# TPS54531.net
KiCad netlist of a schematic drawn in Altium Designer
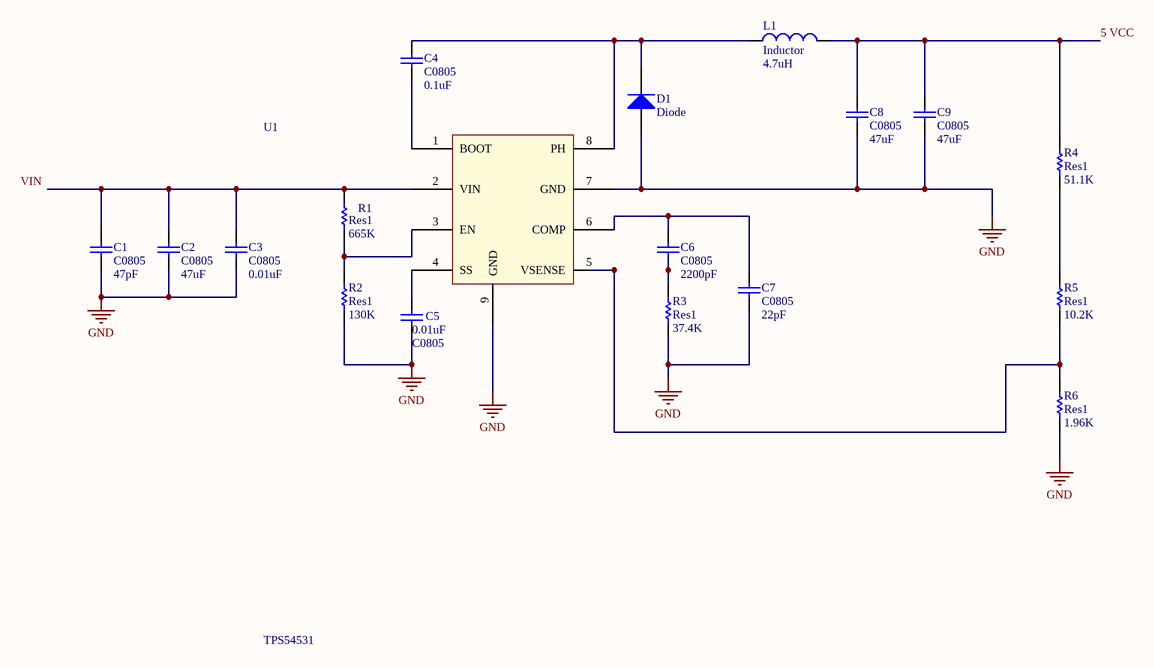
[diagram p0: TPS54531.SchDoc]

(export (version "E")
  (design (tool "Eeschema 10.0.6"))
  (components
    (comp (ref "C1")
      (value "C0805")
      (footprint "0805")
      (description "Ceramic Chip Capacitor - Standard")
      (fields (field (name "ALTIUM_VALUE") "47pF") (field (name "PUBLISHER") "Altium Limited"))
      (libsource (lib "KEMET Chip Capacitor") (part "C0805"))
    )
    (comp (ref "C2")
      (value "C0805")
      (footprint "0805")
      (description "Ceramic Chip Capacitor - Standard")
      (fields (field (name "ALTIUM_VALUE") "47uF") (field (name "PUBLISHER") "Altium Limited"))
      (libsource (lib "KEMET Chip Capacitor") (part "C0805"))
    )
    (comp (ref "C3")
      (value "C0805")
      (footprint "0805")
      (description "Ceramic Chip Capacitor - Standard")
      (fields (field (name "ALTIUM_VALUE") "0.01uF") (field (name "PUBLISHER") "Altium Limited"))
      (libsource (lib "KEMET Chip Capacitor") (part "C0805"))
    )
    (comp (ref "C4")
      (value "C0805")
      (footprint "0805")
      (description "Ceramic Chip Capacitor - Standard")
      (fields (field (name "ALTIUM_VALUE") "0.1uF") (field (name "PUBLISHER") "Altium Limited"))
      (libsource (lib "KEMET Chip Capacitor") (part "C0805"))
    )
    (comp (ref "C5")
      (value "C0805")
      (footprint "0805")
      (description "Ceramic Chip Capacitor - Standard")
      (fields (field (name "ALTIUM_VALUE") "0.01uF") (field (name "PUBLISHER") "Altium Limited"))
      (libsource (lib "KEMET Chip Capacitor") (part "C0805"))
    )
    (comp (ref "C6")
      (value "C0805")
      (footprint "0805")
      (description "Ceramic Chip Capacitor - Standard")
      (fields (field (name "ALTIUM_VALUE") "2200pF") (field (name "PUBLISHER") "Altium Limited"))
      (libsource (lib "KEMET Chip Capacitor") (part "C0805"))
    )
    (comp (ref "C7")
      (value "C0805")
      (footprint "0805")
      (description "Ceramic Chip Capacitor - Standard")
      (fields (field (name "ALTIUM_VALUE") "22pF") (field (name "PUBLISHER") "Altium Limited"))
      (libsource (lib "KEMET Chip Capacitor") (part "C0805"))
    )
    (comp (ref "C8")
      (value "C0805")
      (footprint "0805")
      (description "Ceramic Chip Capacitor - Standard")
      (fields (field (name "ALTIUM_VALUE") "47uF") (field (name "PUBLISHER") "Altium Limited"))
      (libsource (lib "KEMET Chip Capacitor") (part "C0805"))
    )
    (comp (ref "C9")
      (value "C0805")
      (footprint "0805")
      (description "Ceramic Chip Capacitor - Standard")
      (fields (field (name "ALTIUM_VALUE") "47uF") (field (name "PUBLISHER") "Altium Limited"))
      (libsource (lib "KEMET Chip Capacitor") (part "C0805"))
    )
    (comp (ref "D1")
      (value "Diode")
      (footprint "SMC")
      (description "Default Diode")
      (fields (field (name "PUBLISHER") "Altium Limited"))
      (libsource (lib "Miscellaneous Devices") (part "Diode"))
    )
    (comp (ref "L1")
      (value "Inductor")
      (footprint "0402-A")
      (fields (field (name "ALTIUM_VALUE") "4.7uH") (field (name "PUBLISHER") "Altium Limited"))
      (libsource (lib "Miscellaneous Devices") (part "Inductor"))
    )
    (comp (ref "R1")
      (value "Res1")
      (footprint "AXIAL-0.3")
      (description "Resistor")
      (fields (field (name "ALTIUM_VALUE") "665K") (field (name "PUBLISHER") "Altium Limited"))
      (libsource (lib "Miscellaneous Devices") (part "Res1"))
    )
    (comp (ref "R2")
      (value "Res1")
      (footprint "AXIAL-0.3")
      (description "Resistor")
      (fields (field (name "ALTIUM_VALUE") "130K") (field (name "PUBLISHER") "Altium Limited"))
      (libsource (lib "Miscellaneous Devices") (part "Res1"))
    )
    (comp (ref "R3")
      (value "Res1")
      (footprint "AXIAL-0.3")
      (description "Resistor")
      (fields (field (name "ALTIUM_VALUE") "37.4K") (field (name "PUBLISHER") "Altium Limited"))
      (libsource (lib "Miscellaneous Devices") (part "Res1"))
    )
    (comp (ref "R4")
      (value "Res1")
      (footprint "AXIAL-0.3")
      (description "Resistor")
      (fields (field (name "ALTIUM_VALUE") "51.1K") (field (name "PUBLISHER") "Altium Limited"))
      (libsource (lib "Miscellaneous Devices") (part "Res1"))
    )
    (comp (ref "R5")
      (value "Res1")
      (footprint "AXIAL-0.3")
      (description "Resistor")
      (fields (field (name "ALTIUM_VALUE") "10.2K") (field (name "PUBLISHER") "Altium Limited"))
      (libsource (lib "Miscellaneous Devices") (part "Res1"))
    )
    (comp (ref "R6")
      (value "Res1")
      (footprint "AXIAL-0.3")
      (description "Resistor")
      (fields (field (name "ALTIUM_VALUE") "1.96K") (field (name "PUBLISHER") "Altium Limited"))
      (libsource (lib "Miscellaneous Devices") (part "Res1"))
    )
    (comp (ref "U1") (value "TPS54531") (libsource (lib "PowerPadSchem") (part "Component_1")))
  )
  (nets
    (net (code "1") (name "/5 VCC") (class "Default")
      (node (ref "C8") (pin "2") (pinfunction "2_2") (pintype "passive"))
      (node (ref "C9") (pin "2") (pinfunction "2_2") (pintype "passive"))
      (node (ref "L1") (pin "2") (pinfunction "2_2") (pintype "passive"))
      (node (ref "R4") (pin "2") (pinfunction "2_2") (pintype "passive"))
    )
    (net (code "3") (name "GND") (class "Default")
      (node (ref "C1") (pin "1") (pinfunction "1_1") (pintype "passive"))
      (node (ref "C2") (pin "1") (pinfunction "1_1") (pintype "passive"))
      (node (ref "C3") (pin "1") (pinfunction "1_1") (pintype "passive"))
      (node (ref "C5") (pin "1") (pinfunction "1_1") (pintype "passive"))
      (node (ref "C7") (pin "1") (pinfunction "1_1") (pintype "passive"))
      (node (ref "C8") (pin "1") (pinfunction "1_1") (pintype "passive"))
      (node (ref "C9") (pin "1") (pinfunction "1_1") (pintype "passive"))
      (node (ref "D1") (pin "1") (pinfunction "A_1") (pintype "passive"))
      (node (ref "R2") (pin "1") (pinfunction "1_1") (pintype "passive"))
      (node (ref "R3") (pin "1") (pinfunction "1_1") (pintype "passive"))
      (node (ref "R6") (pin "1") (pinfunction "1_1") (pintype "passive"))
      (node (ref "U1") (pin "7") (pinfunction "GND_7") (pintype "passive"))
      (node (ref "U1") (pin "9") (pinfunction "GND_9") (pintype "passive"))
    )
    (net (code "4") (name "Net-(C6-Pad1)") (class "Default")
      (node (ref "C6") (pin "1") (pinfunction "1_1") (pintype "passive"))
      (node (ref "R3") (pin "2") (pinfunction "2_2") (pintype "passive"))
    )
    (net (code "5") (name "Net-(D1-K)") (class "Default")
      (node (ref "C4") (pin "2") (pinfunction "2_2") (pintype "passive"))
      (node (ref "D1") (pin "2") (pinfunction "K_2") (pintype "passive"))
      (node (ref "L1") (pin "1") (pinfunction "1_1") (pintype "passive"))
      (node (ref "U1") (pin "8") (pinfunction "PH_8") (pintype "passive"))
    )
    (net (code "6") (name "Net-(R4-Pad1)") (class "Default")
      (node (ref "R4") (pin "1") (pinfunction "1_1") (pintype "passive"))
      (node (ref "R5") (pin "2") (pinfunction "2_2") (pintype "passive"))
    )
    (net (code "7") (name "Net-(U1-BOOT)") (class "Default")
      (node (ref "C4") (pin "1") (pinfunction "1_1") (pintype "passive"))
      (node (ref "U1") (pin "1") (pinfunction "BOOT_1") (pintype "passive"))
    )
    (net (code "8") (name "Net-(U1-COMP)") (class "Default")
      (node (ref "C6") (pin "2") (pinfunction "2_2") (pintype "passive"))
      (node (ref "C7") (pin "2") (pinfunction "2_2") (pintype "passive"))
      (node (ref "U1") (pin "6") (pinfunction "COMP_6") (pintype "passive"))
    )
    (net (code "9") (name "Net-(U1-EN)") (class "Default")
      (node (ref "R1") (pin "1") (pinfunction "1_1") (pintype "passive"))
      (node (ref "R2") (pin "2") (pinfunction "2_2") (pintype "passive"))
      (node (ref "U1") (pin "3") (pinfunction "EN_3") (pintype "passive"))
    )
    (net (code "10") (name "Net-(U1-SS)") (class "Default")
      (node (ref "C5") (pin "2") (pinfunction "2_2") (pintype "passive"))
      (node (ref "U1") (pin "4") (pinfunction "SS_4") (pintype "passive"))
    )
    (net (code "11") (name "Net-(U1-VIN)") (class "Default")
      (node (ref "C1") (pin "2") (pinfunction "2_2") (pintype "passive"))
      (node (ref "C2") (pin "2") (pinfunction "2_2") (pintype "passive"))
      (node (ref "C3") (pin "2") (pinfunction "2_2") (pintype "passive"))
      (node (ref "R1") (pin "2") (pinfunction "2_2") (pintype "passive"))
      (node (ref "U1") (pin "2") (pinfunction "VIN_2") (pintype "passive"))
    )
    (net (code "12") (name "Net-(U1-VSENSE)") (class "Default")
      (node (ref "R5") (pin "1") (pinfunction "1_1") (pintype "passive"))
      (node (ref "R6") (pin "2") (pinfunction "2_2") (pintype "passive"))
      (node (ref "U1") (pin "5") (pinfunction "VSENSE_5") (pintype "passive"))
    )
  )
)
